# Retrolite_CM4_-_Left_PCB.net
KiCad netlist of a schematic drawn in EAGLE
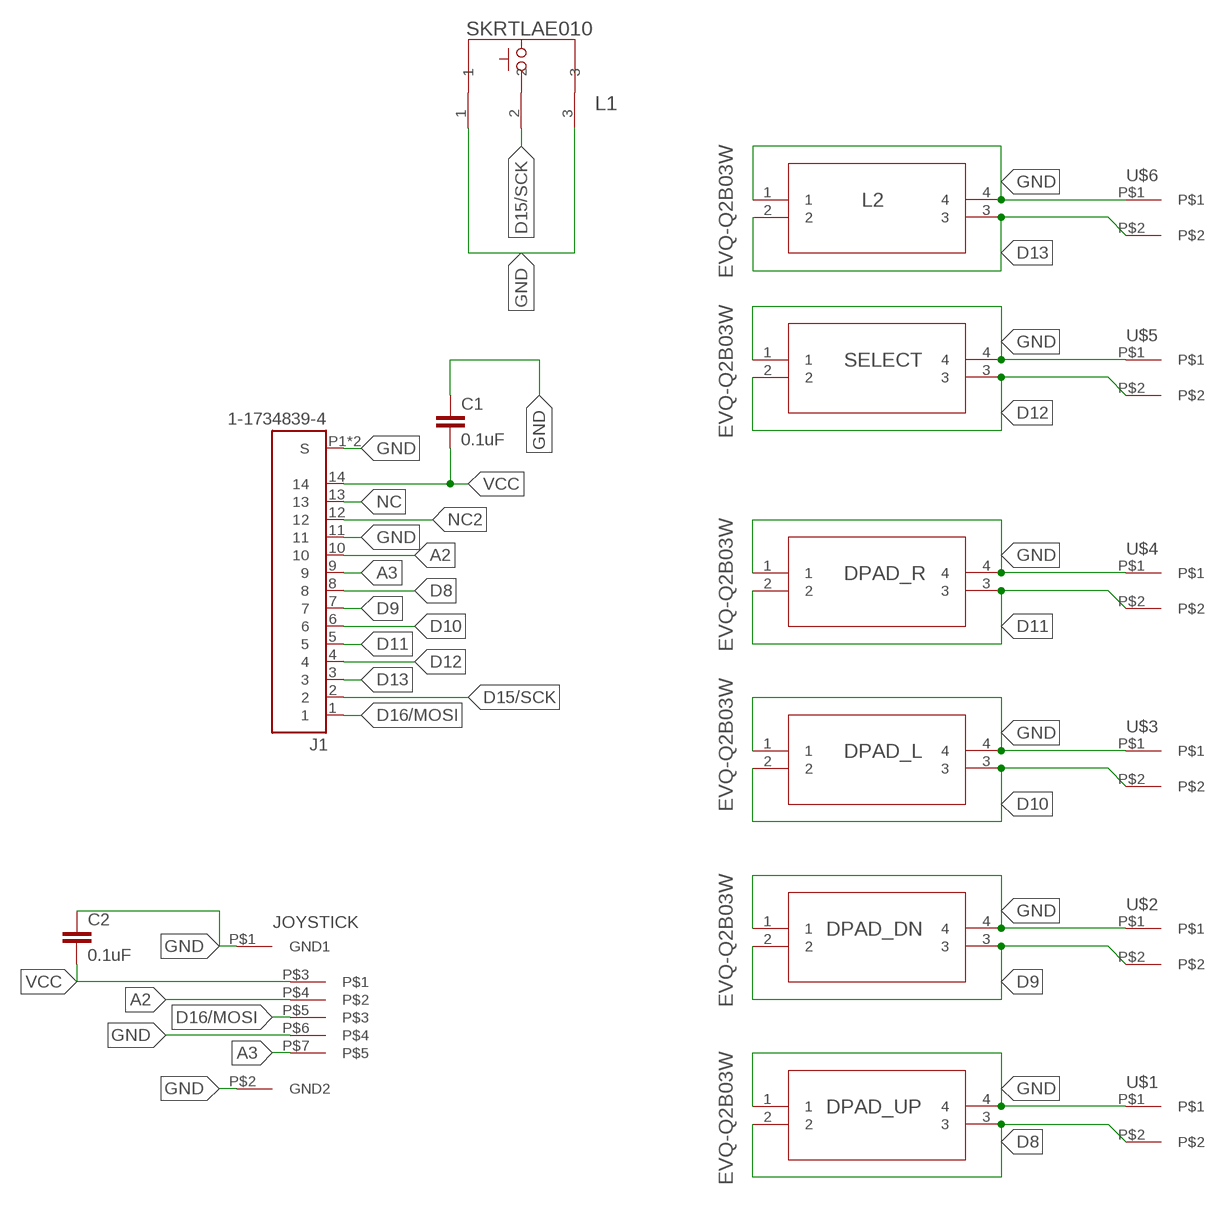
[diagram p0: schematic, sheet 1]

(export (version "E")
  (design (tool "Eeschema 10.0.6"))
  (components
    (comp (ref "C1")
      (value "0.1uF")
      (footprint "eagle-import:0603")
      (libsource (lib "eagle-import") (part "0.1UF-0603-25V-5%"))
    )
    (comp (ref "C2")
      (value "0.1uF")
      (footprint "eagle-import:0603")
      (libsource (lib "eagle-import") (part "0.1UF-0603-25V-5%"))
    )
    (comp (ref "DPAD_DN")
      (value "EVQ-Q2B03W")
      (footprint "eagle-import:EVQQ2_3")
      (fields (field (name "MF") "Panasonic Electronic") (field (name "MP") "EVQQ2B03W"))
      (libsource (lib "eagle-import") (part "EVQ-Q2B03W"))
    )
    (comp (ref "DPAD_L")
      (value "EVQ-Q2B03W")
      (footprint "eagle-import:EVQQ2_3")
      (fields (field (name "MF") "Panasonic Electronic") (field (name "MP") "EVQQ2B03W"))
      (libsource (lib "eagle-import") (part "EVQ-Q2B03W"))
    )
    (comp (ref "DPAD_R")
      (value "EVQ-Q2B03W")
      (footprint "eagle-import:EVQQ2_3")
      (fields (field (name "MF") "Panasonic Electronic") (field (name "MP") "EVQQ2B03W"))
      (libsource (lib "eagle-import") (part "EVQ-Q2B03W"))
    )
    (comp (ref "DPAD_UP")
      (value "EVQ-Q2B03W")
      (footprint "eagle-import:EVQQ2_3")
      (fields (field (name "MF") "Panasonic Electronic") (field (name "MP") "EVQQ2B03W"))
      (libsource (lib "eagle-import") (part "EVQ-Q2B03W"))
    )
    (comp (ref "J1")
      (value "1-1734839-4")
      (footprint "eagle-import:TE_1-1734839-4")
      (fields (field (name "DIGI-KEY_PART_NUMBER") "A100295CT-ND") (field (name "MF") "TE Connectivity"))
      (libsource (lib "eagle-import") (part "1-1734839-4"))
    )
    (comp (ref "JOYSTICK")
      (value "0545500571")
      (footprint "eagle-import:0545500571")
      (libsource (lib "eagle-import") (part "0545500571"))
    )
    (comp (ref "L1")
      (value "SKRTLAE010")
      (footprint "eagle-import:SW3_SKRTLAE010_ALPS")
      (fields (field (name "COPYRIGHT") "Copyright (C) 2016 Accelerated Designs. All rights reserved"))
      (libsource (lib "eagle-import") (part "SKRTLAE010"))
    )
    (comp (ref "L2")
      (value "EVQ-Q2B03W")
      (footprint "eagle-import:EVQQ2_3")
      (fields (field (name "MF") "Panasonic Electronic") (field (name "MP") "EVQQ2B03W"))
      (libsource (lib "eagle-import") (part "EVQ-Q2B03W"))
    )
    (comp (ref "SELECT")
      (value "EVQ-Q2B03W")
      (footprint "eagle-import:EVQQ2_3")
      (fields (field (name "MF") "Panasonic Electronic") (field (name "MP") "EVQQ2B03W"))
      (libsource (lib "eagle-import") (part "EVQ-Q2B03W"))
    )
    (comp (ref "U$1")
      (value "MEMBRANEBUTTON")
      (footprint "eagle-import:MEMBRANEBUTTON")
      (libsource (lib "eagle-import") (part "MEMBRANEBUTTON"))
    )
    (comp (ref "U$2")
      (value "MEMBRANEBUTTON")
      (footprint "eagle-import:MEMBRANEBUTTON")
      (libsource (lib "eagle-import") (part "MEMBRANEBUTTON"))
    )
    (comp (ref "U$3")
      (value "MEMBRANEBUTTON")
      (footprint "eagle-import:MEMBRANEBUTTON")
      (libsource (lib "eagle-import") (part "MEMBRANEBUTTON"))
    )
    (comp (ref "U$4")
      (value "MEMBRANEBUTTON")
      (footprint "eagle-import:MEMBRANEBUTTON")
      (libsource (lib "eagle-import") (part "MEMBRANEBUTTON"))
    )
    (comp (ref "U$5")
      (value "MEMBRANEBUTTON")
      (footprint "eagle-import:MEMBRANEBUTTON")
      (libsource (lib "eagle-import") (part "MEMBRANEBUTTON"))
    )
    (comp (ref "U$6")
      (value "MEMBRANEBUTTON")
      (footprint "eagle-import:MEMBRANEBUTTON")
      (libsource (lib "eagle-import") (part "MEMBRANEBUTTON"))
    )
  )
  (nets
    (net (code "1") (name "A2") (class "Default")
      (node (ref "J1") (pin "10") (pinfunction "10_10") (pintype "passive"))
      (node (ref "JOYSTICK") (pin "P$4") (pinfunction "P$2_P$4") (pintype "bidirectional"))
    )
    (net (code "2") (name "A3") (class "Default")
      (node (ref "J1") (pin "9") (pinfunction "9_9") (pintype "passive"))
      (node (ref "JOYSTICK") (pin "P$7") (pinfunction "P$5_P$7") (pintype "bidirectional"))
    )
    (net (code "3") (name "D8") (class "Default")
      (node (ref "DPAD_UP") (pin "2") (pinfunction "2_2") (pintype "passive"))
      (node (ref "DPAD_UP") (pin "3") (pinfunction "3_3") (pintype "passive"))
      (node (ref "J1") (pin "8") (pinfunction "8_8") (pintype "passive"))
      (node (ref "U$1") (pin "P$2") (pinfunction "P$2_P$2") (pintype "bidirectional"))
    )
    (net (code "4") (name "D9") (class "Default")
      (node (ref "DPAD_DN") (pin "2") (pinfunction "2_2") (pintype "passive"))
      (node (ref "DPAD_DN") (pin "3") (pinfunction "3_3") (pintype "passive"))
      (node (ref "J1") (pin "7") (pinfunction "7_7") (pintype "passive"))
      (node (ref "U$2") (pin "P$2") (pinfunction "P$2_P$2") (pintype "bidirectional"))
    )
    (net (code "5") (name "D10") (class "Default")
      (node (ref "DPAD_L") (pin "2") (pinfunction "2_2") (pintype "passive"))
      (node (ref "DPAD_L") (pin "3") (pinfunction "3_3") (pintype "passive"))
      (node (ref "J1") (pin "6") (pinfunction "6_6") (pintype "passive"))
      (node (ref "U$3") (pin "P$2") (pinfunction "P$2_P$2") (pintype "bidirectional"))
    )
    (net (code "6") (name "D11") (class "Default")
      (node (ref "DPAD_R") (pin "2") (pinfunction "2_2") (pintype "passive"))
      (node (ref "DPAD_R") (pin "3") (pinfunction "3_3") (pintype "passive"))
      (node (ref "J1") (pin "5") (pinfunction "5_5") (pintype "passive"))
      (node (ref "U$4") (pin "P$2") (pinfunction "P$2_P$2") (pintype "bidirectional"))
    )
    (net (code "7") (name "D12") (class "Default")
      (node (ref "J1") (pin "4") (pinfunction "4_4") (pintype "passive"))
      (node (ref "SELECT") (pin "2") (pinfunction "2_2") (pintype "passive"))
      (node (ref "SELECT") (pin "3") (pinfunction "3_3") (pintype "passive"))
      (node (ref "U$5") (pin "P$2") (pinfunction "P$2_P$2") (pintype "bidirectional"))
    )
    (net (code "8") (name "D13") (class "Default")
      (node (ref "J1") (pin "3") (pinfunction "3_3") (pintype "passive"))
      (node (ref "L2") (pin "2") (pinfunction "2_2") (pintype "passive"))
      (node (ref "L2") (pin "3") (pinfunction "3_3") (pintype "passive"))
      (node (ref "U$6") (pin "P$2") (pinfunction "P$2_P$2") (pintype "bidirectional"))
    )
    (net (code "9") (name "D15{slash}SCK") (class "Default")
      (node (ref "J1") (pin "2") (pinfunction "2_2") (pintype "passive"))
      (node (ref "L1") (pin "2") (pinfunction "2_2") (pintype "passive"))
    )
    (net (code "10") (name "D16{slash}MOSI") (class "Default")
      (node (ref "J1") (pin "1") (pinfunction "1_1") (pintype "passive"))
      (node (ref "JOYSTICK") (pin "P$5") (pinfunction "P$3_P$5") (pintype "bidirectional"))
    )
    (net (code "11") (name "GND") (class "Default")
      (node (ref "C1") (pin "1") (pinfunction "1_1") (pintype "passive"))
      (node (ref "C2") (pin "1") (pinfunction "1_1") (pintype "passive"))
      (node (ref "DPAD_DN") (pin "1") (pinfunction "1_1") (pintype "passive"))
      (node (ref "DPAD_DN") (pin "4") (pinfunction "4_4") (pintype "passive"))
      (node (ref "DPAD_L") (pin "1") (pinfunction "1_1") (pintype "passive"))
      (node (ref "DPAD_L") (pin "4") (pinfunction "4_4") (pintype "passive"))
      (node (ref "DPAD_R") (pin "1") (pinfunction "1_1") (pintype "passive"))
      (node (ref "DPAD_R") (pin "4") (pinfunction "4_4") (pintype "passive"))
      (node (ref "DPAD_UP") (pin "1") (pinfunction "1_1") (pintype "passive"))
      (node (ref "DPAD_UP") (pin "4") (pinfunction "4_4") (pintype "passive"))
      (node (ref "J1") (pin "11") (pinfunction "11_11") (pintype "passive"))
      (node (ref "J1") (pin "P1") (pinfunction "S_P1") (pintype "passive"))
      (node (ref "J1") (pin "P2") (pinfunction "S_P2") (pintype "passive"))
      (node (ref "JOYSTICK") (pin "P$1") (pinfunction "GND1_P$1") (pintype "bidirectional"))
      (node (ref "JOYSTICK") (pin "P$2") (pinfunction "GND2_P$2") (pintype "bidirectional"))
      (node (ref "JOYSTICK") (pin "P$6") (pinfunction "P$4_P$6") (pintype "bidirectional"))
      (node (ref "L1") (pin "1") (pinfunction "1_1") (pintype "passive"))
      (node (ref "L1") (pin "3") (pinfunction "3_3") (pintype "passive"))
      (node (ref "L2") (pin "1") (pinfunction "1_1") (pintype "passive"))
      (node (ref "L2") (pin "4") (pinfunction "4_4") (pintype "passive"))
      (node (ref "SELECT") (pin "1") (pinfunction "1_1") (pintype "passive"))
      (node (ref "SELECT") (pin "4") (pinfunction "4_4") (pintype "passive"))
      (node (ref "U$1") (pin "P$1") (pinfunction "P$1_P$1") (pintype "bidirectional"))
      (node (ref "U$2") (pin "P$1") (pinfunction "P$1_P$1") (pintype "bidirectional"))
      (node (ref "U$3") (pin "P$1") (pinfunction "P$1_P$1") (pintype "bidirectional"))
      (node (ref "U$4") (pin "P$1") (pinfunction "P$1_P$1") (pintype "bidirectional"))
      (node (ref "U$5") (pin "P$1") (pinfunction "P$1_P$1") (pintype "bidirectional"))
      (node (ref "U$6") (pin "P$1") (pinfunction "P$1_P$1") (pintype "bidirectional"))
    )
    (net (code "12") (name "NC") (class "Default")
      (node (ref "J1") (pin "13") (pinfunction "13_13") (pintype "passive"))
    )
    (net (code "13") (name "NC2") (class "Default")
      (node (ref "J1") (pin "12") (pinfunction "12_12") (pintype "passive"))
    )
    (net (code "14") (name "VCC") (class "Default")
      (node (ref "C1") (pin "2") (pinfunction "2_2") (pintype "passive"))
      (node (ref "C2") (pin "2") (pinfunction "2_2") (pintype "passive"))
      (node (ref "J1") (pin "14") (pinfunction "14_14") (pintype "passive"))
      (node (ref "JOYSTICK") (pin "P$3") (pinfunction "P$1_P$3") (pintype "bidirectional"))
    )
  )
)
